# HBridge.net
KiCad netlist of a schematic drawn in Altium Designer
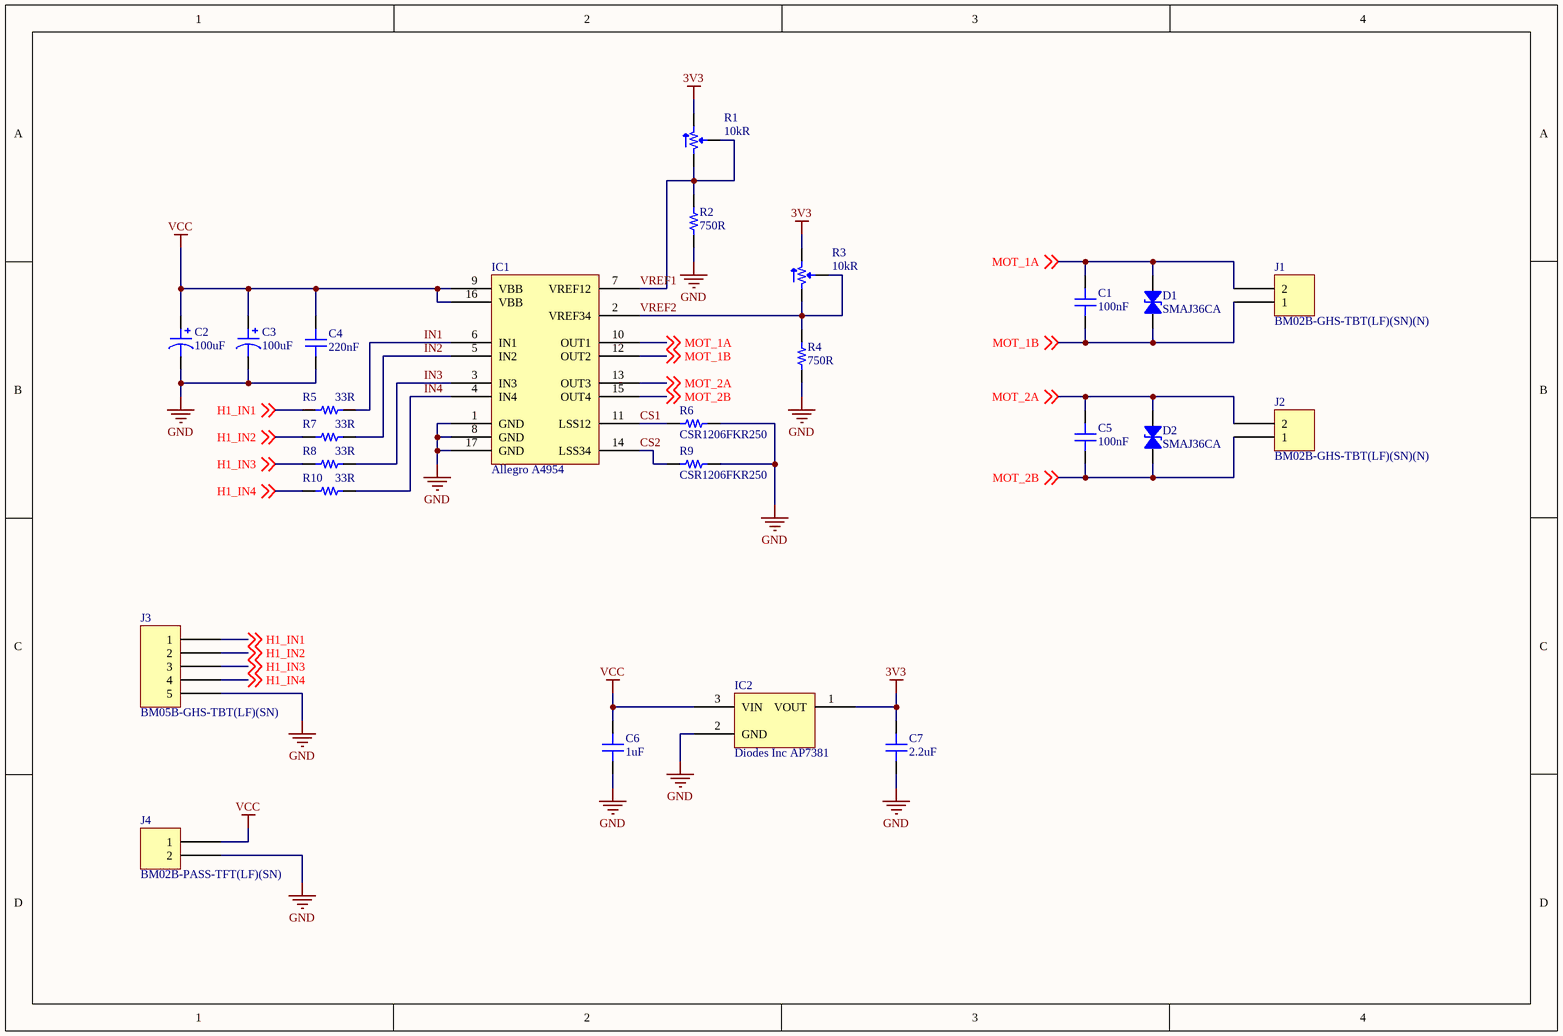
[diagram p0: HBridge.SchDoc]

(export (version "E")
  (design (tool "Eeschema 10.0.6"))
  (components
    (comp (ref "C1")
      (value "100nF")
      (footprint "CAP 0402/1005")
      (description "SMT Capacitor")
      (fields (field (name "TOLERANCE") "10%"))
      (libsource (lib "SCH - PASSIVES - CAPACITOR") (part "Capacitor"))
    )
    (comp (ref "C2")
      (value "100uF")
      (footprint "CAP ALUM 8.3MM")
      (description "SMT Polarised Capacitor")
      (fields (field (name "TOLERANCE") "20%") (field (name "VOLTAGE") "50V"))
      (libsource (lib "SCH - PASSIVES - POLARISED CAPACITOR") (part "Polarised Capacitor"))
    )
    (comp (ref "C3")
      (value "100uF")
      (footprint "CAP ALUM 8.3MM")
      (description "SMT Polarised Capacitor")
      (fields (field (name "TOLERANCE") "20%") (field (name "VOLTAGE") "50V"))
      (libsource (lib "SCH - PASSIVES - POLARISED CAPACITOR") (part "Polarised Capacitor"))
    )
    (comp (ref "C4")
      (value "220nF")
      (footprint "CAP 0402/1005")
      (description "SMT Capacitor")
      (fields (field (name "TOLERANCE") "10%"))
      (libsource (lib "SCH - PASSIVES - CAPACITOR") (part "Capacitor"))
    )
    (comp (ref "C5")
      (value "100nF")
      (footprint "CAP 0402/1005")
      (description "SMT Capacitor")
      (fields (field (name "TOLERANCE") "10%"))
      (libsource (lib "SCH - PASSIVES - CAPACITOR") (part "Capacitor"))
    )
    (comp (ref "C6")
      (value "1uF")
      (footprint "CAP 0603/1608")
      (description "SMT Capacitor")
      (fields (field (name "TOLERANCE") "10%"))
      (libsource (lib "SCH - PASSIVES - CAPACITOR") (part "Capacitor"))
    )
    (comp (ref "C7")
      (value "2.2uF")
      (footprint "CAP 0603/1608")
      (description "SMT Capacitor")
      (fields (field (name "TOLERANCE") "10%") (field (name "VOLTAGE") "10V"))
      (libsource (lib "SCH - PASSIVES - CAPACITOR") (part "Capacitor"))
    )
    (comp (ref "D1")
      (value "SMAJ36CA")
      (footprint "Bourns DO214AC SMA")
      (description "Bidirectional Zener Diode")
      (libsource (lib "SCH - DIODES - DIODE ZENER BIDIRECTIONAL") (part "Diode Zener Bidirectional"))
    )
    (comp (ref "D2")
      (value "SMAJ36CA")
      (footprint "Bourns DO214AC SMA")
      (description "Bidirectional Zener Diode")
      (libsource (lib "SCH - DIODES - DIODE ZENER BIDIRECTIONAL") (part "Diode Zener Bidirectional"))
    )
    (comp (ref "IC1")
      (value "Allegro A4954")
      (footprint "ALLEGRO TSSOP-16EP LP")
      (libsource (lib "SCH - DRIVER - MOTOR - ALLEGRO A4954") (part "Allegro A4954"))
    )
    (comp (ref "IC2")
      (value "Diodes Inc AP7381")
      (footprint "DIODES INC SOT-89")
      (description "150mA Low quiescent current fast transient low drop out linear regulator")
      (libsource (lib "SCH - POWER - LINEAR VREG - DIODES INC AP7381") (part "Diodes Inc AP7381"))
    )
    (comp (ref "J1")
      (value "BM02B-GHS-TBT(LF)(SN)(N)")
      (footprint "JST BM02B-GHS-TBT")
      (libsource (lib "") (part "2 Pin_1"))
    )
    (comp (ref "J2")
      (value "BM02B-GHS-TBT(LF)(SN)(N)")
      (footprint "JST BM02B-GHS-TBT")
      (libsource (lib "") (part "2 Pin_1"))
    )
    (comp (ref "J3")
      (value "BM05B-GHS-TBT(LF)(SN)")
      (footprint "JST BM05B-GHS-TBT")
      (libsource (lib "SCH - CONNECTORS - 5 PIN") (part "5 Pin"))
    )
    (comp (ref "J4")
      (value "BM02B-PASS-TFT(LF)(SN)")
      (footprint "JST BM02B-GHS-TBT")
      (libsource (lib "SCH - CONNECTORS - 2 PIN") (part "2 Pin"))
    )
    (comp (ref "R1")
      (value "10kR")
      (footprint "POT BOURNS TRIMPOT TC33X-1")
      (description "Potentiometer")
      (fields (field (name "TOLERANCE") "25%"))
      (libsource (lib "SCH - PASSIVES - POTENTIOMETER") (part "Potentiometer"))
    )
    (comp (ref "R2")
      (value "750R")
      (footprint "RES 0402/1005")
      (description "SMT Resistor")
      (fields (field (name "TOLERANCE") "1%"))
      (libsource (lib "SCH - PASSIVES - RESISTOR") (part "Resistor"))
    )
    (comp (ref "R3")
      (value "10kR")
      (footprint "POT BOURNS TRIMPOT TC33X-1")
      (description "Potentiometer")
      (fields (field (name "TOLERANCE") "25%"))
      (libsource (lib "SCH - PASSIVES - POTENTIOMETER") (part "Potentiometer"))
    )
    (comp (ref "R4")
      (value "750R")
      (footprint "RES 0402/1005")
      (description "SMT Resistor")
      (fields (field (name "TOLERANCE") "1%"))
      (libsource (lib "SCH - PASSIVES - RESISTOR") (part "Resistor"))
    )
    (comp (ref "R5")
      (value "33R")
      (footprint "RES 0402/1005")
      (description "SMT Resistor")
      (fields (field (name "TOLERANCE") "5%"))
      (libsource (lib "SCH - PASSIVES - RESISTOR") (part "Resistor"))
    )
    (comp (ref "R6")
      (value "CSR1206FKR250")
      (footprint "STACKPOLE CSR1210")
      (description "SMT Resistor")
      (fields (field (name "TOLERANCE") "1%"))
      (libsource (lib "SCH - PASSIVES - RESISTOR") (part "Resistor"))
    )
    (comp (ref "R7")
      (value "33R")
      (footprint "RES 0402/1005")
      (description "SMT Resistor")
      (fields (field (name "TOLERANCE") "5%"))
      (libsource (lib "SCH - PASSIVES - RESISTOR") (part "Resistor"))
    )
    (comp (ref "R8")
      (value "33R")
      (footprint "RES 0402/1005")
      (description "SMT Resistor")
      (fields (field (name "TOLERANCE") "5%"))
      (libsource (lib "SCH - PASSIVES - RESISTOR") (part "Resistor"))
    )
    (comp (ref "R9")
      (value "CSR1206FKR250")
      (footprint "STACKPOLE CSR1210")
      (description "SMT Resistor")
      (fields (field (name "TOLERANCE") "1%"))
      (libsource (lib "SCH - PASSIVES - RESISTOR") (part "Resistor"))
    )
    (comp (ref "R10")
      (value "33R")
      (footprint "RES 0402/1005")
      (description "SMT Resistor")
      (fields (field (name "TOLERANCE") "5%"))
      (libsource (lib "SCH - PASSIVES - RESISTOR") (part "Resistor"))
    )
  )
  (nets
    (net (code "1") (name "/CS1") (class "Default")
      (node (ref "IC1") (pin "11") (pinfunction "LSS12_11") (pintype "passive"))
      (node (ref "R6") (pin "1") (pinfunction "1_1") (pintype "passive"))
    )
    (net (code "2") (name "/CS2") (class "Default")
      (node (ref "IC1") (pin "14") (pinfunction "LSS34_14") (pintype "passive"))
      (node (ref "R9") (pin "1") (pinfunction "1_1") (pintype "passive"))
    )
    (net (code "3") (name "/IN1") (class "Default")
      (node (ref "IC1") (pin "6") (pinfunction "IN1_6") (pintype "passive"))
      (node (ref "R5") (pin "2") (pinfunction "2_2") (pintype "passive"))
    )
    (net (code "4") (name "/IN2") (class "Default")
      (node (ref "IC1") (pin "5") (pinfunction "IN2_5") (pintype "passive"))
      (node (ref "R7") (pin "2") (pinfunction "2_2") (pintype "passive"))
    )
    (net (code "5") (name "/IN3") (class "Default")
      (node (ref "IC1") (pin "3") (pinfunction "IN3_3") (pintype "passive"))
      (node (ref "R8") (pin "2") (pinfunction "2_2") (pintype "passive"))
    )
    (net (code "6") (name "/IN4") (class "Default")
      (node (ref "IC1") (pin "4") (pinfunction "IN4_4") (pintype "passive"))
      (node (ref "R10") (pin "2") (pinfunction "2_2") (pintype "passive"))
    )
    (net (code "7") (name "/VREF1") (class "Default")
      (node (ref "IC1") (pin "7") (pinfunction "VREF12_7") (pintype "passive"))
      (node (ref "R1") (pin "1") (pinfunction "1_1") (pintype "passive"))
      (node (ref "R1") (pin "2") (pinfunction "2_2") (pintype "passive"))
      (node (ref "R2") (pin "2") (pinfunction "2_2") (pintype "passive"))
    )
    (net (code "8") (name "/VREF2") (class "Default")
      (node (ref "IC1") (pin "2") (pinfunction "VREF34_2") (pintype "passive"))
      (node (ref "R3") (pin "1") (pinfunction "1_1") (pintype "passive"))
      (node (ref "R3") (pin "2") (pinfunction "2_2") (pintype "passive"))
      (node (ref "R4") (pin "2") (pinfunction "2_2") (pintype "passive"))
    )
    (net (code "9") (name "3V3") (class "Default")
      (node (ref "C7") (pin "2") (pinfunction "2_2") (pintype "passive"))
      (node (ref "IC2") (pin "1") (pinfunction "VOUT_1") (pintype "passive"))
      (node (ref "R1") (pin "3") (pinfunction "3_3") (pintype "passive"))
      (node (ref "R3") (pin "3") (pinfunction "3_3") (pintype "passive"))
    )
    (net (code "10") (name "GND") (class "Default")
      (node (ref "C2") (pin "2") (pinfunction "2_2") (pintype "passive"))
      (node (ref "C3") (pin "2") (pinfunction "2_2") (pintype "passive"))
      (node (ref "C4") (pin "2") (pinfunction "2_2") (pintype "passive"))
      (node (ref "C6") (pin "1") (pinfunction "1_1") (pintype "passive"))
      (node (ref "C7") (pin "1") (pinfunction "1_1") (pintype "passive"))
      (node (ref "IC1") (pin "1") (pinfunction "GND_1") (pintype "passive"))
      (node (ref "IC1") (pin "17") (pinfunction "GND_17") (pintype "passive"))
      (node (ref "IC1") (pin "8") (pinfunction "GND_8") (pintype "passive"))
      (node (ref "IC2") (pin "2") (pinfunction "GND_2") (pintype "passive"))
      (node (ref "J3") (pin "5") (pinfunction "5_5") (pintype "passive"))
      (node (ref "J4") (pin "2") (pinfunction "2_2") (pintype "passive"))
      (node (ref "R2") (pin "1") (pinfunction "1_1") (pintype "passive"))
      (node (ref "R4") (pin "1") (pinfunction "1_1") (pintype "passive"))
      (node (ref "R6") (pin "2") (pinfunction "2_2") (pintype "passive"))
      (node (ref "R9") (pin "2") (pinfunction "2_2") (pintype "passive"))
    )
    (net (code "11") (name "H1_IN1") (class "Default")
      (node (ref "J3") (pin "1") (pinfunction "1_1") (pintype "passive"))
      (node (ref "R5") (pin "1") (pinfunction "1_1") (pintype "passive"))
    )
    (net (code "12") (name "H1_IN2") (class "Default")
      (node (ref "J3") (pin "2") (pinfunction "2_2") (pintype "passive"))
      (node (ref "R7") (pin "1") (pinfunction "1_1") (pintype "passive"))
    )
    (net (code "13") (name "H1_IN3") (class "Default")
      (node (ref "J3") (pin "3") (pinfunction "3_3") (pintype "passive"))
      (node (ref "R8") (pin "1") (pinfunction "1_1") (pintype "passive"))
    )
    (net (code "14") (name "H1_IN4") (class "Default")
      (node (ref "J3") (pin "4") (pinfunction "4_4") (pintype "passive"))
      (node (ref "R10") (pin "1") (pinfunction "1_1") (pintype "passive"))
    )
    (net (code "15") (name "MOT_1A") (class "Default")
      (node (ref "C1") (pin "1") (pinfunction "1_1") (pintype "passive"))
      (node (ref "D1") (pin "2") (pinfunction "2_2") (pintype "passive"))
      (node (ref "IC1") (pin "10") (pinfunction "OUT1_10") (pintype "passive"))
      (node (ref "J1") (pin "2") (pinfunction "2_2") (pintype "passive"))
    )
    (net (code "16") (name "MOT_1B") (class "Default")
      (node (ref "C1") (pin "2") (pinfunction "2_2") (pintype "passive"))
      (node (ref "D1") (pin "1") (pinfunction "1_1") (pintype "passive"))
      (node (ref "IC1") (pin "12") (pinfunction "OUT2_12") (pintype "passive"))
      (node (ref "J1") (pin "1") (pinfunction "1_1") (pintype "passive"))
    )
    (net (code "17") (name "MOT_2A") (class "Default")
      (node (ref "C5") (pin "1") (pinfunction "1_1") (pintype "passive"))
      (node (ref "D2") (pin "2") (pinfunction "2_2") (pintype "passive"))
      (node (ref "IC1") (pin "13") (pinfunction "OUT3_13") (pintype "passive"))
      (node (ref "J2") (pin "2") (pinfunction "2_2") (pintype "passive"))
    )
    (net (code "18") (name "MOT_2B") (class "Default")
      (node (ref "C5") (pin "2") (pinfunction "2_2") (pintype "passive"))
      (node (ref "D2") (pin "1") (pinfunction "1_1") (pintype "passive"))
      (node (ref "IC1") (pin "15") (pinfunction "OUT4_15") (pintype "passive"))
      (node (ref "J2") (pin "1") (pinfunction "1_1") (pintype "passive"))
    )
    (net (code "19") (name "VCC") (class "Default")
      (node (ref "C2") (pin "1") (pinfunction "1_1") (pintype "passive"))
      (node (ref "C3") (pin "1") (pinfunction "1_1") (pintype "passive"))
      (node (ref "C4") (pin "1") (pinfunction "1_1") (pintype "passive"))
      (node (ref "C6") (pin "2") (pinfunction "2_2") (pintype "passive"))
      (node (ref "IC1") (pin "16") (pinfunction "VBB_16") (pintype "passive"))
      (node (ref "IC1") (pin "9") (pinfunction "VBB_9") (pintype "passive"))
      (node (ref "IC2") (pin "3") (pinfunction "VIN_3") (pintype "passive"))
      (node (ref "J4") (pin "1") (pinfunction "1_1") (pintype "passive"))
    )
  )
)
